# DRV8833.net
KiCad netlist of a schematic drawn in Altium Designer
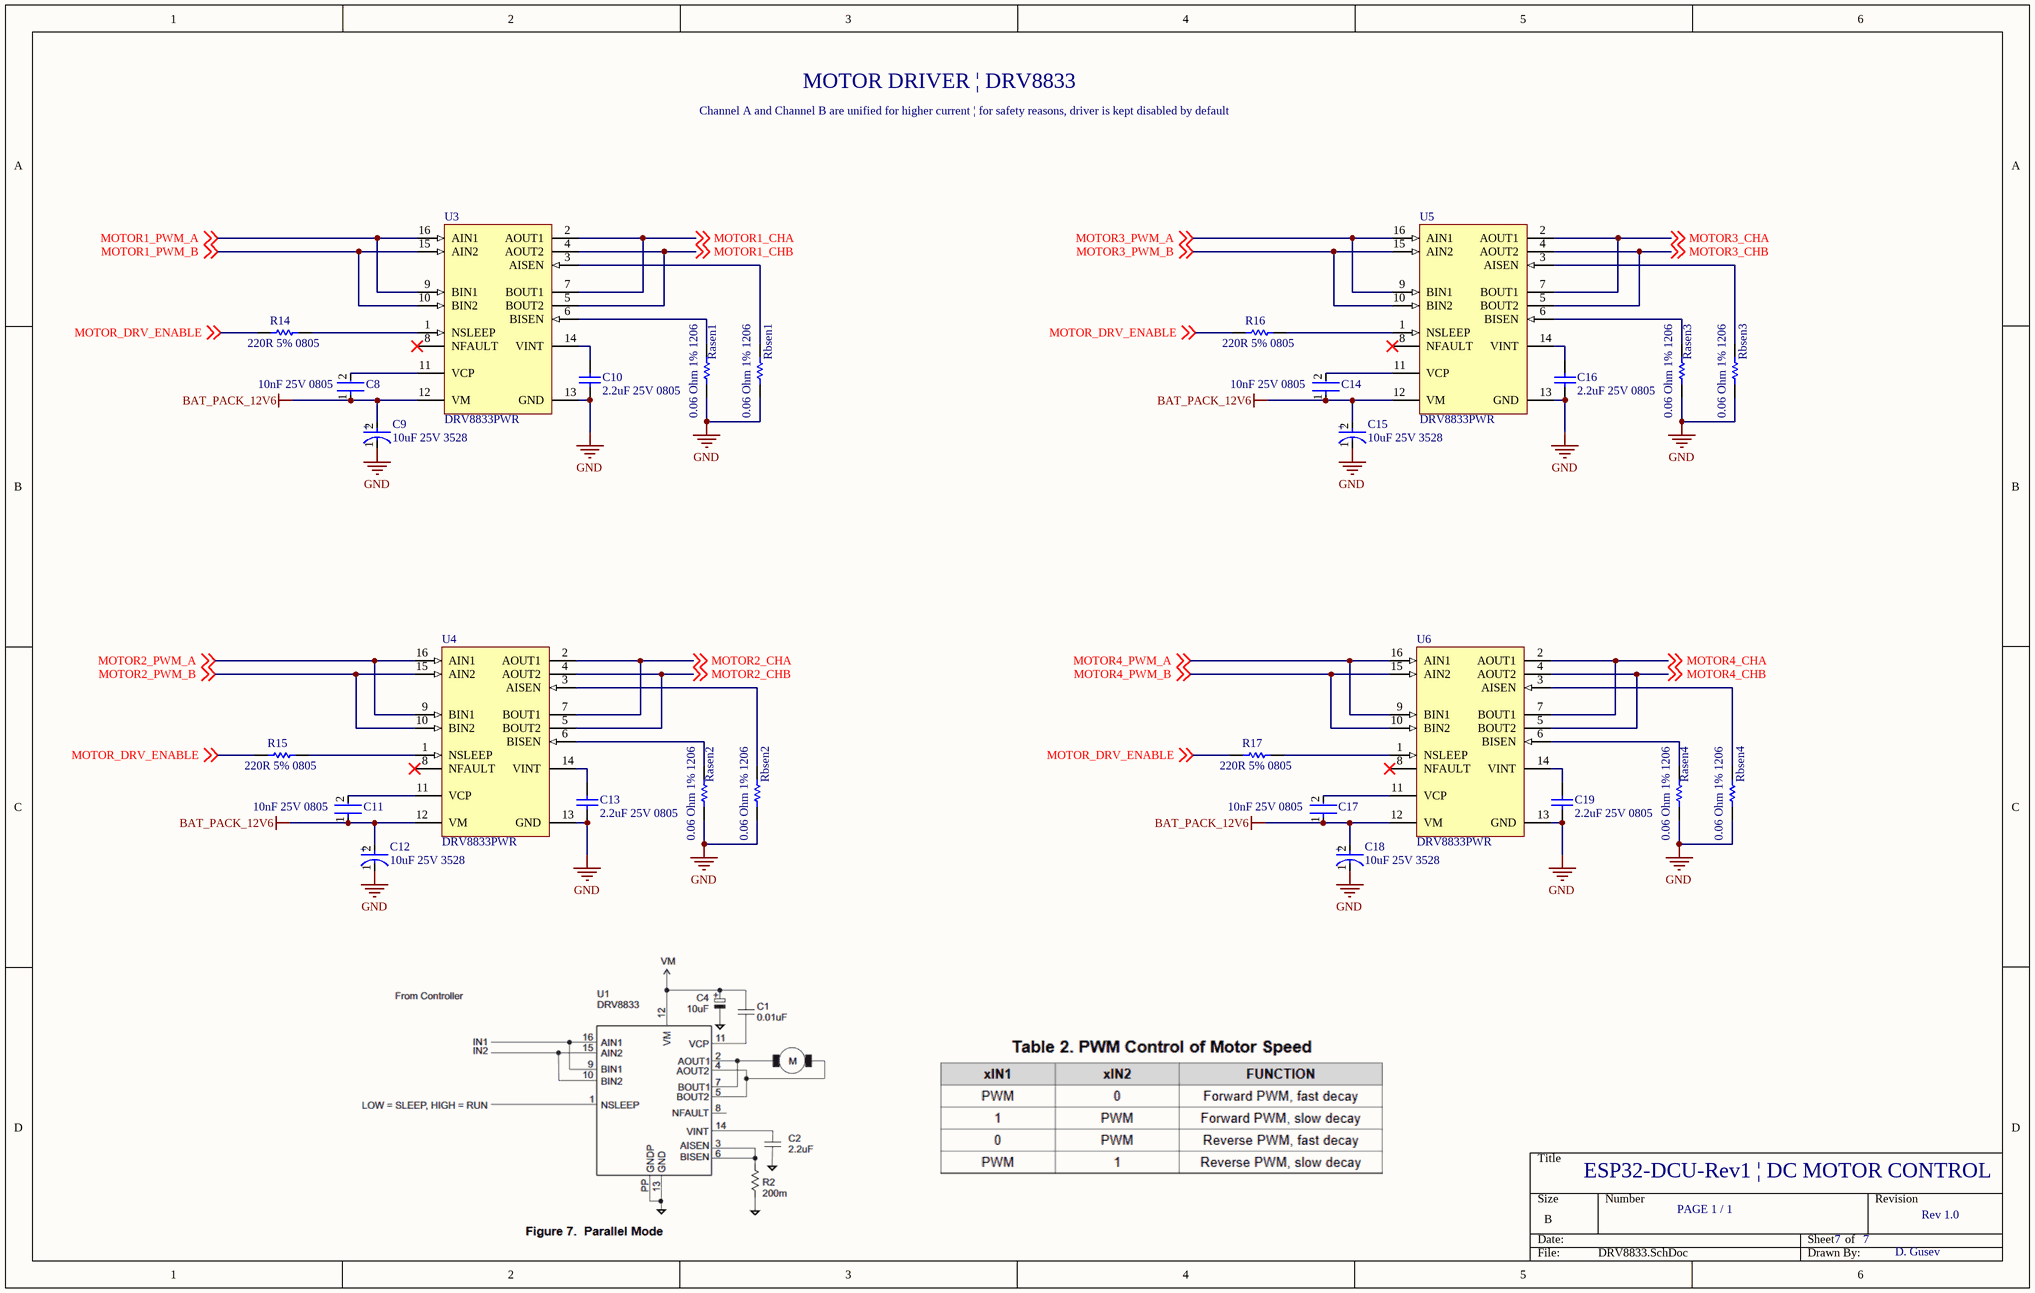
[diagram p0: DRV8833.SchDoc]

(export (version "E")
  (design (tool "Eeschema 10.0.6"))
  (components
    (comp (ref "C8")
      (value "10nF 25V 0805")
      (footprint "FP-C0805C-DN-MFG")
      (description "CAP CER 10000PF 25V 5% NP0 0805")
      (fields
        (field (name "OCTOPART") "https://octopart.com/c0805c103j3gactu-kemet-12563663")
        (field (name "TOLERANCE") "0.05")
      )
      (libsource (lib "Altium Content Vault") (part "b4654b650e69147ec39a6b967a45e02"))
    )
    (comp (ref "C9")
      (value "10uF 25V 3528")
      (footprint "FP-T491B106K025AT-MFG")
      (description "CAP TANT 10UF 10% 25V 1411")
      (fields (field (name "VOLTAGE") "25V") (field (name "TOLERANCE") "10%"))
      (libsource (lib "Altium Content Vault") (part "a00bbbee19879c290e62620ae7e47b1"))
    )
    (comp (ref "C10")
      (value "2.2uF 25V 0805")
      (footprint "CAPC2013X135X45ML10T25")
      (fields (field (name "PART NUMBER") "GRM21BF51E225ZA01L") (field (name "MANUFACTURER") "Murata"))
      (libsource (lib "Altium Content Vault") (part "CAP"))
    )
    (comp (ref "C11")
      (value "10nF 25V 0805")
      (footprint "FP-C0805C-DN-MFG")
      (description "CAP CER 10000PF 25V 5% NP0 0805")
      (fields
        (field (name "OCTOPART") "https://octopart.com/c0805c103j3gactu-kemet-12563663")
        (field (name "TOLERANCE") "0.05")
      )
      (libsource (lib "Altium Content Vault") (part "b4654b650e69147ec39a6b967a45e02"))
    )
    (comp (ref "C12")
      (value "10uF 25V 3528")
      (footprint "FP-T491B106K025AT-MFG")
      (description "CAP TANT 10UF 10% 25V 1411")
      (fields (field (name "VOLTAGE") "25V") (field (name "TOLERANCE") "10%"))
      (libsource (lib "Altium Content Vault") (part "a00bbbee19879c290e62620ae7e47b1"))
    )
    (comp (ref "C13")
      (value "2.2uF 25V 0805")
      (footprint "CAPC2013X135X45ML10T25")
      (fields (field (name "PART NUMBER") "GRM21BF51E225ZA01L") (field (name "MANUFACTURER") "Murata"))
      (libsource (lib "Altium Content Vault") (part "CAP"))
    )
    (comp (ref "C14")
      (value "10nF 25V 0805")
      (footprint "FP-C0805C-DN-MFG")
      (description "CAP CER 10000PF 25V 5% NP0 0805")
      (fields
        (field (name "OCTOPART") "https://octopart.com/c0805c103j3gactu-kemet-12563663")
        (field (name "TOLERANCE") "0.05")
      )
      (libsource (lib "Altium Content Vault") (part "b4654b650e69147ec39a6b967a45e02"))
    )
    (comp (ref "C15")
      (value "10uF 25V 3528")
      (footprint "FP-T491B106K025AT-MFG")
      (description "CAP TANT 10UF 10% 25V 1411")
      (fields (field (name "VOLTAGE") "25V") (field (name "TOLERANCE") "10%"))
      (libsource (lib "Altium Content Vault") (part "a00bbbee19879c290e62620ae7e47b1"))
    )
    (comp (ref "C16")
      (value "2.2uF 25V 0805")
      (footprint "CAPC2013X135X45ML10T25")
      (fields (field (name "PART NUMBER") "GRM21BF51E225ZA01L") (field (name "MANUFACTURER") "Murata"))
      (libsource (lib "Altium Content Vault") (part "CAP"))
    )
    (comp (ref "C17")
      (value "10nF 25V 0805")
      (footprint "FP-C0805C-DN-MFG")
      (description "CAP CER 10000PF 25V 5% NP0 0805")
      (fields
        (field (name "OCTOPART") "https://octopart.com/c0805c103j3gactu-kemet-12563663")
        (field (name "TOLERANCE") "0.05")
      )
      (libsource (lib "Altium Content Vault") (part "b4654b650e69147ec39a6b967a45e02"))
    )
    (comp (ref "C18")
      (value "10uF 25V 3528")
      (footprint "FP-T491B106K025AT-MFG")
      (description "CAP TANT 10UF 10% 25V 1411")
      (fields (field (name "VOLTAGE") "25V") (field (name "TOLERANCE") "10%"))
      (libsource (lib "Altium Content Vault") (part "a00bbbee19879c290e62620ae7e47b1"))
    )
    (comp (ref "C19")
      (value "2.2uF 25V 0805")
      (footprint "CAPC2013X135X45ML10T25")
      (fields (field (name "PART NUMBER") "GRM21BF51E225ZA01L") (field (name "MANUFACTURER") "Murata"))
      (libsource (lib "Altium Content Vault") (part "CAP"))
    )
    (comp (ref "R14")
      (value "220R 5% 0805")
      (footprint "RESC2013X60X40NL20T25")
      (fields (field (name "MANUFACTURER") "Panasonic") (field (name "PART NUMBER") "ERA6AEB221V"))
      (libsource (lib "Altium Content Vault") (part "RES"))
    )
    (comp (ref "R15")
      (value "220R 5% 0805")
      (footprint "RESC2013X60X40NL20T25")
      (fields (field (name "MANUFACTURER") "Panasonic") (field (name "PART NUMBER") "ERA6AEB221V"))
      (libsource (lib "Altium Content Vault") (part "RES"))
    )
    (comp (ref "R16")
      (value "220R 5% 0805")
      (footprint "RESC2013X60X40NL20T25")
      (fields (field (name "MANUFACTURER") "Panasonic") (field (name "PART NUMBER") "ERA6AEB221V"))
      (libsource (lib "Altium Content Vault") (part "RES"))
    )
    (comp (ref "R17")
      (value "220R 5% 0805")
      (footprint "RESC2013X60X40NL20T25")
      (fields (field (name "MANUFACTURER") "Panasonic") (field (name "PART NUMBER") "ERA6AEB221V"))
      (libsource (lib "Altium Content Vault") (part "RES"))
    )
    (comp (ref "Rasen1")
      (value "0.06 Ohm 1% 1206")
      (footprint "RESC3216X89X51NL25T25")
      (fields (field (name "MANUFACTURER") "Vishay Dale") (field (name "PART NUMBER") "WSL1206R0600FEA"))
      (libsource (lib "Altium Content Vault") (part "RES"))
    )
    (comp (ref "Rasen2")
      (value "0.06 Ohm 1% 1206")
      (footprint "RESC3216X89X51NL25T25")
      (fields (field (name "MANUFACTURER") "Vishay Dale") (field (name "PART NUMBER") "WSL1206R0600FEA"))
      (libsource (lib "Altium Content Vault") (part "RES"))
    )
    (comp (ref "Rasen3")
      (value "0.06 Ohm 1% 1206")
      (footprint "RESC3216X89X51NL25T25")
      (fields (field (name "MANUFACTURER") "Vishay Dale") (field (name "PART NUMBER") "WSL1206R0600FEA"))
      (libsource (lib "Altium Content Vault") (part "RES"))
    )
    (comp (ref "Rasen4")
      (value "0.06 Ohm 1% 1206")
      (footprint "RESC3216X89X51NL25T25")
      (fields (field (name "MANUFACTURER") "Vishay Dale") (field (name "PART NUMBER") "WSL1206R0600FEA"))
      (libsource (lib "Altium Content Vault") (part "RES"))
    )
    (comp (ref "Rbsen1")
      (value "0.06 Ohm 1% 1206")
      (footprint "RESC3216X89X51NL25T25")
      (fields (field (name "MANUFACTURER") "Vishay Dale") (field (name "PART NUMBER") "WSL1206R0600FEA"))
      (libsource (lib "Altium Content Vault") (part "RES"))
    )
    (comp (ref "Rbsen2")
      (value "0.06 Ohm 1% 1206")
      (footprint "RESC3216X89X51NL25T25")
      (fields (field (name "MANUFACTURER") "Vishay Dale") (field (name "PART NUMBER") "WSL1206R0600FEA"))
      (libsource (lib "Altium Content Vault") (part "RES"))
    )
    (comp (ref "Rbsen3")
      (value "0.06 Ohm 1% 1206")
      (footprint "RESC3216X89X51NL25T25")
      (fields (field (name "MANUFACTURER") "Vishay Dale") (field (name "PART NUMBER") "WSL1206R0600FEA"))
      (libsource (lib "Altium Content Vault") (part "RES"))
    )
    (comp (ref "Rbsen4")
      (value "0.06 Ohm 1% 1206")
      (footprint "RESC3216X89X51NL25T25")
      (fields (field (name "MANUFACTURER") "Vishay Dale") (field (name "PART NUMBER") "WSL1206R0600FEA"))
      (libsource (lib "Altium Content Vault") (part "RES"))
    )
    (comp (ref "U3")
      (value "DRV8833PWR")
      (footprint "PW0016A_L")
      (fields (field (name "MANUFACTURER") "Texas Instruments"))
      (libsource (lib "Altium Content Vault") (part "TI-DRV8833PW-16"))
    )
    (comp (ref "U4")
      (value "DRV8833PWR")
      (footprint "PW0016A_L")
      (fields (field (name "MANUFACTURER") "Texas Instruments"))
      (libsource (lib "Altium Content Vault") (part "TI-DRV8833PW-16"))
    )
    (comp (ref "U5")
      (value "DRV8833PWR")
      (footprint "PW0016A_L")
      (fields (field (name "MANUFACTURER") "Texas Instruments"))
      (libsource (lib "Altium Content Vault") (part "TI-DRV8833PW-16"))
    )
    (comp (ref "U6")
      (value "DRV8833PWR")
      (footprint "PW0016A_L")
      (fields (field (name "MANUFACTURER") "Texas Instruments"))
      (libsource (lib "Altium Content Vault") (part "TI-DRV8833PW-16"))
    )
  )
  (nets
    (net (code "1") (name "BAT_PACK_12V6") (class "Default")
      (node (ref "C11") (pin "1") (pinfunction "1_1") (pintype "passive"))
      (node (ref "C12") (pin "2") (pinfunction "A_2") (pintype "passive"))
      (node (ref "C14") (pin "1") (pinfunction "1_1") (pintype "passive"))
      (node (ref "C15") (pin "2") (pinfunction "A_2") (pintype "passive"))
      (node (ref "C17") (pin "1") (pinfunction "1_1") (pintype "passive"))
      (node (ref "C18") (pin "2") (pinfunction "A_2") (pintype "passive"))
      (node (ref "C8") (pin "1") (pinfunction "1_1") (pintype "passive"))
      (node (ref "C9") (pin "2") (pinfunction "A_2") (pintype "passive"))
      (node (ref "U3") (pin "12") (pinfunction "VM_12") (pintype "power_in"))
      (node (ref "U4") (pin "12") (pinfunction "VM_12") (pintype "power_in"))
      (node (ref "U5") (pin "12") (pinfunction "VM_12") (pintype "power_in"))
      (node (ref "U6") (pin "12") (pinfunction "VM_12") (pintype "power_in"))
    )
    (net (code "2") (name "GND") (class "Default")
      (node (ref "C10") (pin "1") (pinfunction "1_1") (pintype "passive"))
      (node (ref "C12") (pin "1") (pinfunction "C_1") (pintype "passive"))
      (node (ref "C13") (pin "1") (pinfunction "1_1") (pintype "passive"))
      (node (ref "C15") (pin "1") (pinfunction "C_1") (pintype "passive"))
      (node (ref "C16") (pin "1") (pinfunction "1_1") (pintype "passive"))
      (node (ref "C18") (pin "1") (pinfunction "C_1") (pintype "passive"))
      (node (ref "C19") (pin "1") (pinfunction "1_1") (pintype "passive"))
      (node (ref "C9") (pin "1") (pinfunction "C_1") (pintype "passive"))
      (node (ref "Rasen1") (pin "1") (pinfunction "1_1") (pintype "passive"))
      (node (ref "Rasen2") (pin "1") (pinfunction "1_1") (pintype "passive"))
      (node (ref "Rasen3") (pin "1") (pinfunction "1_1") (pintype "passive"))
      (node (ref "Rasen4") (pin "1") (pinfunction "1_1") (pintype "passive"))
      (node (ref "Rbsen1") (pin "1") (pinfunction "1_1") (pintype "passive"))
      (node (ref "Rbsen2") (pin "1") (pinfunction "1_1") (pintype "passive"))
      (node (ref "Rbsen3") (pin "1") (pinfunction "1_1") (pintype "passive"))
      (node (ref "Rbsen4") (pin "1") (pinfunction "1_1") (pintype "passive"))
      (node (ref "U3") (pin "13") (pinfunction "GND_13") (pintype "power_in"))
      (node (ref "U4") (pin "13") (pinfunction "GND_13") (pintype "power_in"))
      (node (ref "U5") (pin "13") (pinfunction "GND_13") (pintype "power_in"))
      (node (ref "U6") (pin "13") (pinfunction "GND_13") (pintype "power_in"))
    )
    (net (code "3") (name "MOTOR1_CHA") (class "Default")
      (node (ref "U3") (pin "2") (pinfunction "AOUT1_2") (pintype "tri_state"))
      (node (ref "U3") (pin "7") (pinfunction "BOUT1_7") (pintype "tri_state"))
    )
    (net (code "4") (name "MOTOR1_CHB") (class "Default")
      (node (ref "U3") (pin "4") (pinfunction "AOUT2_4") (pintype "tri_state"))
      (node (ref "U3") (pin "5") (pinfunction "BOUT2_5") (pintype "tri_state"))
    )
    (net (code "5") (name "MOTOR1_PWM_A") (class "Default")
      (node (ref "U3") (pin "16") (pinfunction "AIN1_16") (pintype "input"))
      (node (ref "U3") (pin "9") (pinfunction "BIN1_9") (pintype "input"))
    )
    (net (code "6") (name "MOTOR1_PWM_B") (class "Default")
      (node (ref "U3") (pin "10") (pinfunction "BIN2_10") (pintype "input"))
      (node (ref "U3") (pin "15") (pinfunction "AIN2_15") (pintype "input"))
    )
    (net (code "7") (name "MOTOR2_CHA") (class "Default")
      (node (ref "U4") (pin "2") (pinfunction "AOUT1_2") (pintype "tri_state"))
      (node (ref "U4") (pin "7") (pinfunction "BOUT1_7") (pintype "tri_state"))
    )
    (net (code "8") (name "MOTOR2_CHB") (class "Default")
      (node (ref "U4") (pin "4") (pinfunction "AOUT2_4") (pintype "tri_state"))
      (node (ref "U4") (pin "5") (pinfunction "BOUT2_5") (pintype "tri_state"))
    )
    (net (code "9") (name "MOTOR2_PWM_A") (class "Default")
      (node (ref "U4") (pin "16") (pinfunction "AIN1_16") (pintype "input"))
      (node (ref "U4") (pin "9") (pinfunction "BIN1_9") (pintype "input"))
    )
    (net (code "10") (name "MOTOR2_PWM_B") (class "Default")
      (node (ref "U4") (pin "10") (pinfunction "BIN2_10") (pintype "input"))
      (node (ref "U4") (pin "15") (pinfunction "AIN2_15") (pintype "input"))
    )
    (net (code "11") (name "MOTOR3_CHA") (class "Default")
      (node (ref "U5") (pin "2") (pinfunction "AOUT1_2") (pintype "tri_state"))
      (node (ref "U5") (pin "7") (pinfunction "BOUT1_7") (pintype "tri_state"))
    )
    (net (code "12") (name "MOTOR3_CHB") (class "Default")
      (node (ref "U5") (pin "4") (pinfunction "AOUT2_4") (pintype "tri_state"))
      (node (ref "U5") (pin "5") (pinfunction "BOUT2_5") (pintype "tri_state"))
    )
    (net (code "13") (name "MOTOR3_PWM_A") (class "Default")
      (node (ref "U5") (pin "16") (pinfunction "AIN1_16") (pintype "input"))
      (node (ref "U5") (pin "9") (pinfunction "BIN1_9") (pintype "input"))
    )
    (net (code "14") (name "MOTOR3_PWM_B") (class "Default")
      (node (ref "U5") (pin "10") (pinfunction "BIN2_10") (pintype "input"))
      (node (ref "U5") (pin "15") (pinfunction "AIN2_15") (pintype "input"))
    )
    (net (code "15") (name "MOTOR4_CHA") (class "Default")
      (node (ref "U6") (pin "2") (pinfunction "AOUT1_2") (pintype "tri_state"))
      (node (ref "U6") (pin "7") (pinfunction "BOUT1_7") (pintype "tri_state"))
    )
    (net (code "16") (name "MOTOR4_CHB") (class "Default")
      (node (ref "U6") (pin "4") (pinfunction "AOUT2_4") (pintype "tri_state"))
      (node (ref "U6") (pin "5") (pinfunction "BOUT2_5") (pintype "tri_state"))
    )
    (net (code "17") (name "MOTOR4_PWM_A") (class "Default")
      (node (ref "U6") (pin "16") (pinfunction "AIN1_16") (pintype "input"))
      (node (ref "U6") (pin "9") (pinfunction "BIN1_9") (pintype "input"))
    )
    (net (code "18") (name "MOTOR4_PWM_B") (class "Default")
      (node (ref "U6") (pin "10") (pinfunction "BIN2_10") (pintype "input"))
      (node (ref "U6") (pin "15") (pinfunction "AIN2_15") (pintype "input"))
    )
    (net (code "19") (name "MOTOR_DRV_ENABLE") (class "Default")
      (node (ref "R14") (pin "1") (pinfunction "1_1") (pintype "passive"))
      (node (ref "R15") (pin "1") (pinfunction "1_1") (pintype "passive"))
      (node (ref "R16") (pin "1") (pinfunction "1_1") (pintype "passive"))
      (node (ref "R17") (pin "1") (pinfunction "1_1") (pintype "passive"))
    )
    (net (code "20") (name "Net-(U3-AISEN)") (class "Default")
      (node (ref "Rbsen1") (pin "2") (pinfunction "2_2") (pintype "passive"))
      (node (ref "U3") (pin "3") (pinfunction "AISEN_3") (pintype "input"))
    )
    (net (code "21") (name "Net-(U3-BISEN)") (class "Default")
      (node (ref "Rasen1") (pin "2") (pinfunction "2_2") (pintype "passive"))
      (node (ref "U3") (pin "6") (pinfunction "BISEN_6") (pintype "input"))
    )
    (net (code "22") (name "Net-(U3-NSLEEP)") (class "Default")
      (node (ref "R14") (pin "2") (pinfunction "2_2") (pintype "passive"))
      (node (ref "U3") (pin "1") (pinfunction "NSLEEP_1") (pintype "input"))
    )
    (net (code "23") (name "Net-(U3-VCP)") (class "Default")
      (node (ref "C8") (pin "2") (pinfunction "2_2") (pintype "passive"))
      (node (ref "U3") (pin "11") (pinfunction "VCP_11") (pintype "passive"))
    )
    (net (code "24") (name "Net-(U3-VINT)") (class "Default")
      (node (ref "C10") (pin "2") (pinfunction "2_2") (pintype "passive"))
      (node (ref "U3") (pin "14") (pinfunction "VINT_14") (pintype "passive"))
    )
    (net (code "25") (name "Net-(U4-AISEN)") (class "Default")
      (node (ref "Rbsen2") (pin "2") (pinfunction "2_2") (pintype "passive"))
      (node (ref "U4") (pin "3") (pinfunction "AISEN_3") (pintype "input"))
    )
    (net (code "26") (name "Net-(U4-BISEN)") (class "Default")
      (node (ref "Rasen2") (pin "2") (pinfunction "2_2") (pintype "passive"))
      (node (ref "U4") (pin "6") (pinfunction "BISEN_6") (pintype "input"))
    )
    (net (code "27") (name "Net-(U4-NSLEEP)") (class "Default")
      (node (ref "R15") (pin "2") (pinfunction "2_2") (pintype "passive"))
      (node (ref "U4") (pin "1") (pinfunction "NSLEEP_1") (pintype "input"))
    )
    (net (code "28") (name "Net-(U4-VCP)") (class "Default")
      (node (ref "C11") (pin "2") (pinfunction "2_2") (pintype "passive"))
      (node (ref "U4") (pin "11") (pinfunction "VCP_11") (pintype "passive"))
    )
    (net (code "29") (name "Net-(U4-VINT)") (class "Default")
      (node (ref "C13") (pin "2") (pinfunction "2_2") (pintype "passive"))
      (node (ref "U4") (pin "14") (pinfunction "VINT_14") (pintype "passive"))
    )
    (net (code "30") (name "Net-(U5-AISEN)") (class "Default")
      (node (ref "Rbsen3") (pin "2") (pinfunction "2_2") (pintype "passive"))
      (node (ref "U5") (pin "3") (pinfunction "AISEN_3") (pintype "input"))
    )
    (net (code "31") (name "Net-(U5-BISEN)") (class "Default")
      (node (ref "Rasen3") (pin "2") (pinfunction "2_2") (pintype "passive"))
      (node (ref "U5") (pin "6") (pinfunction "BISEN_6") (pintype "input"))
    )
    (net (code "32") (name "Net-(U5-NSLEEP)") (class "Default")
      (node (ref "R16") (pin "2") (pinfunction "2_2") (pintype "passive"))
      (node (ref "U5") (pin "1") (pinfunction "NSLEEP_1") (pintype "input"))
    )
    (net (code "33") (name "Net-(U5-VCP)") (class "Default")
      (node (ref "C14") (pin "2") (pinfunction "2_2") (pintype "passive"))
      (node (ref "U5") (pin "11") (pinfunction "VCP_11") (pintype "passive"))
    )
    (net (code "34") (name "Net-(U5-VINT)") (class "Default")
      (node (ref "C16") (pin "2") (pinfunction "2_2") (pintype "passive"))
      (node (ref "U5") (pin "14") (pinfunction "VINT_14") (pintype "passive"))
    )
    (net (code "35") (name "Net-(U6-AISEN)") (class "Default")
      (node (ref "Rbsen4") (pin "2") (pinfunction "2_2") (pintype "passive"))
      (node (ref "U6") (pin "3") (pinfunction "AISEN_3") (pintype "input"))
    )
    (net (code "36") (name "Net-(U6-BISEN)") (class "Default")
      (node (ref "Rasen4") (pin "2") (pinfunction "2_2") (pintype "passive"))
      (node (ref "U6") (pin "6") (pinfunction "BISEN_6") (pintype "input"))
    )
    (net (code "37") (name "Net-(U6-NSLEEP)") (class "Default")
      (node (ref "R17") (pin "2") (pinfunction "2_2") (pintype "passive"))
      (node (ref "U6") (pin "1") (pinfunction "NSLEEP_1") (pintype "input"))
    )
    (net (code "38") (name "Net-(U6-VCP)") (class "Default")
      (node (ref "C17") (pin "2") (pinfunction "2_2") (pintype "passive"))
      (node (ref "U6") (pin "11") (pinfunction "VCP_11") (pintype "passive"))
    )
    (net (code "39") (name "Net-(U6-VINT)") (class "Default")
      (node (ref "C19") (pin "2") (pinfunction "2_2") (pintype "passive"))
      (node (ref "U6") (pin "14") (pinfunction "VINT_14") (pintype "passive"))
    )
    (net (code "40") (name "unconnected-(U3-NFAULT-Pad8)") (class "Default")
      (node (ref "U3") (pin "8") (pinfunction "NFAULT_8") (pintype "open_collector+no_connect"))
    )
    (net (code "41") (name "unconnected-(U4-NFAULT-Pad8)") (class "Default")
      (node (ref "U4") (pin "8") (pinfunction "NFAULT_8") (pintype "open_collector+no_connect"))
    )
    (net (code "42") (name "unconnected-(U5-NFAULT-Pad8)") (class "Default")
      (node (ref "U5") (pin "8") (pinfunction "NFAULT_8") (pintype "open_collector+no_connect"))
    )
    (net (code "43") (name "unconnected-(U6-NFAULT-Pad8)") (class "Default")
      (node (ref "U6") (pin "8") (pinfunction "NFAULT_8") (pintype "open_collector+no_connect"))
    )
  )
)
